# main.net
KiCad netlist of a schematic drawn in Altium Designer
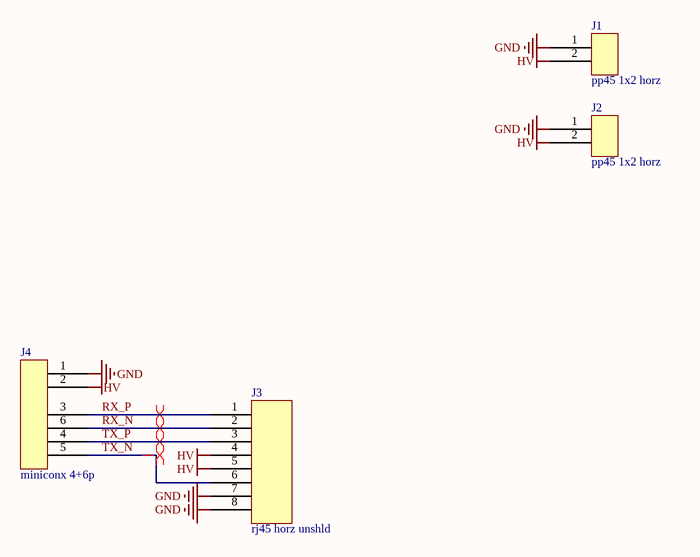
[diagram p0: main.SchDoc]

(export (version "E")
  (design (tool "Eeschema 10.0.6"))
  (components
    (comp (ref "J1")
      (value "pp45 1x2 horz")
      (footprint "CONN PP45 1x2P HORZ")
      (description "Heavy Duty Power Connectors PCB45 HORIZ (TOP) RA LP CONT.")
      (libsource (lib "streetbot") (part "CONN pp45 1x2 horz"))
    )
    (comp (ref "J2")
      (value "pp45 1x2 horz")
      (footprint "CONN PP45 1x2P HORZ")
      (description "Heavy Duty Power Connectors PCB45 HORIZ (TOP) RA LP CONT.")
      (libsource (lib "streetbot") (part "CONN pp45 1x2 horz"))
    )
    (comp (ref "J3")
      (value "rj45 horz unshld")
      (footprint "CONN RJ45 HORZ UNSHLD")
      (description "CONN MOD JACK 8P8C R/A UNSHLD")
      (libsource (lib "streetbot") (part "CONN rj45 horz unshld"))
    )
    (comp (ref "J4")
      (value "miniconx 4+6p")
      (footprint "CONN MINICONX 4+2P")
      (description "Standard Circular Connector PosLck Pnl Mnt#16#22 PC Cont 6MPins 300")
      (libsource (lib "streetbot") (part "CONN miniconx 4+2p vert"))
    )
  )
  (nets
    (net (code "1") (name "/RX_N") (class "Default")
      (node (ref "J3") (pin "2") (pintype "passive"))
      (node (ref "J4") (pin "6") (pintype "passive"))
    )
    (net (code "2") (name "/RX_P") (class "Default")
      (node (ref "J3") (pin "1") (pintype "passive"))
      (node (ref "J4") (pin "3") (pintype "passive"))
    )
    (net (code "3") (name "/TX_N") (class "Default")
      (node (ref "J3") (pin "6") (pintype "passive"))
      (node (ref "J4") (pin "5") (pintype "passive"))
    )
    (net (code "4") (name "/TX_P") (class "Default")
      (node (ref "J3") (pin "3") (pintype "passive"))
      (node (ref "J4") (pin "4") (pintype "passive"))
    )
    (net (code "5") (name "GND") (class "Default")
      (node (ref "J1") (pin "1") (pintype "passive"))
      (node (ref "J2") (pin "1") (pintype "passive"))
      (node (ref "J3") (pin "7") (pintype "passive"))
      (node (ref "J3") (pin "8") (pintype "passive"))
      (node (ref "J4") (pin "1") (pintype "passive"))
    )
    (net (code "6") (name "HV") (class "Default")
      (node (ref "J1") (pin "2") (pintype "passive"))
      (node (ref "J2") (pin "2") (pintype "passive"))
      (node (ref "J3") (pin "4") (pintype "passive"))
      (node (ref "J3") (pin "5") (pintype "passive"))
      (node (ref "J4") (pin "2") (pintype "passive"))
    )
  )
)
